# diferencial-733.net
KiCad netlist of a schematic drawn in EAGLE
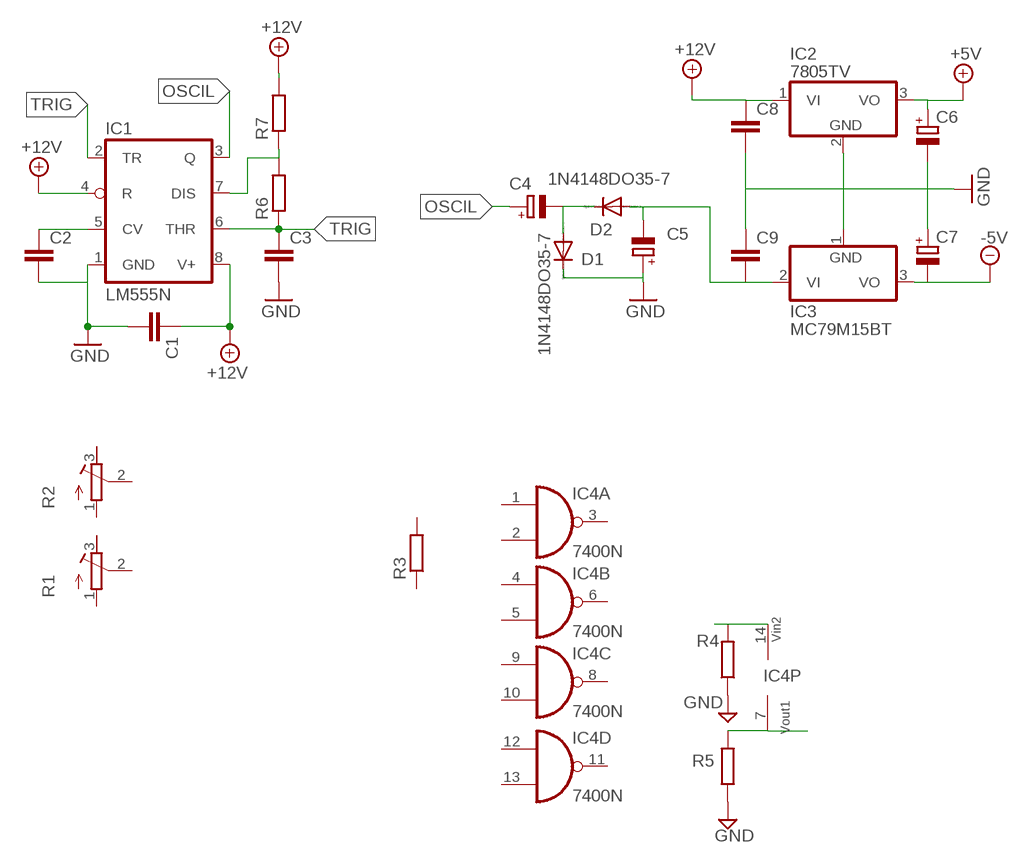
[diagram p0: schematic, sheet 1]

(export (version "E")
  (design (tool "Eeschema 10.0.6"))
  (components
    (comp (ref "C1")
      (value "C-EU050-025X075")
      (footprint "eagle-import:C050-025X075")
      (libsource (lib "eagle-import") (part "C-EU050-025X075"))
    )
    (comp (ref "C2")
      (value "C-EU050-025X075")
      (footprint "eagle-import:C050-025X075")
      (libsource (lib "eagle-import") (part "C-EU050-025X075"))
    )
    (comp (ref "C3")
      (value "C-EU025-025X050")
      (footprint "eagle-import:C025-025X050")
      (libsource (lib "eagle-import") (part "C-EU025-025X050"))
    )
    (comp (ref "C4")
      (value "CPOL-EUE2.5-6")
      (footprint "eagle-import:E2,5-6")
      (libsource (lib "eagle-import") (part "CPOL-EUE2.5-6"))
    )
    (comp (ref "C5")
      (value "CPOL-EUE2.5-7")
      (footprint "eagle-import:E2,5-7")
      (libsource (lib "eagle-import") (part "CPOL-EUE2.5-7"))
    )
    (comp (ref "C6")
      (value "CPOL-EUE2.5-5")
      (footprint "eagle-import:E2,5-5")
      (libsource (lib "eagle-import") (part "CPOL-EUE2.5-5"))
    )
    (comp (ref "C7")
      (value "CPOL-EUE2.5-5")
      (footprint "eagle-import:E2,5-5")
      (libsource (lib "eagle-import") (part "CPOL-EUE2.5-5"))
    )
    (comp (ref "C8")
      (value "C-EU025-025X050")
      (footprint "eagle-import:C025-025X050")
      (libsource (lib "eagle-import") (part "C-EU025-025X050"))
    )
    (comp (ref "C9")
      (value "C-EU025-025X050")
      (footprint "eagle-import:C025-025X050")
      (libsource (lib "eagle-import") (part "C-EU025-025X050"))
    )
    (comp (ref "D1")
      (value "1N4148DO35-7")
      (footprint "eagle-import:DO35-7")
      (libsource (lib "eagle-import") (part "1N4148DO35-7"))
    )
    (comp (ref "D2")
      (value "1N4148DO35-7")
      (footprint "eagle-import:DO35-7")
      (libsource (lib "eagle-import") (part "1N4148DO35-7"))
    )
    (comp (ref "IC1")
      (value "LM555N")
      (footprint "eagle-import:DIL08")
      (libsource (lib "eagle-import") (part "555NLM"))
    )
    (comp (ref "IC2")
      (value "7805TV")
      (footprint "eagle-import:TO220V")
      (libsource (lib "eagle-import") (part "78TV05"))
    )
    (comp (ref "IC3")
      (value "MC79M15BT")
      (footprint "eagle-import:TO220V")
      (libsource (lib "eagle-import") (part "MC79MT15B"))
    )
    (comp (ref "IC4")
      (value "7400N")
      (footprint "eagle-import:DIL14")
      (libsource (lib "eagle-import") (part "7400N"))
    )
    (comp (ref "R1")
      (value "R-TRIMM64W")
      (footprint "eagle-import:RTRIM64W")
      (libsource (lib "eagle-import") (part "R-TRIMM64W"))
    )
    (comp (ref "R2")
      (value "R-TRIMM64W")
      (footprint "eagle-import:RTRIM64W")
      (libsource (lib "eagle-import") (part "R-TRIMM64W"))
    )
    (comp (ref "R3")
      (value "R-EU_0207/7")
      (footprint "eagle-import:0207_7")
      (libsource (lib "eagle-import") (part "R-EU_0207/7"))
    )
    (comp (ref "R4")
      (value "R-EU_0207/7")
      (footprint "eagle-import:0207_7")
      (libsource (lib "eagle-import") (part "R-EU_0207/7"))
    )
    (comp (ref "R5")
      (value "R-EU_0207/7")
      (footprint "eagle-import:0207_7")
      (libsource (lib "eagle-import") (part "R-EU_0207/7"))
    )
    (comp (ref "R6")
      (value "R-EU_0207/7")
      (footprint "eagle-import:0207_7")
      (libsource (lib "eagle-import") (part "R-EU_0207/7"))
    )
    (comp (ref "R7")
      (value "R-EU_0207/7")
      (footprint "eagle-import:0207_7")
      (libsource (lib "eagle-import") (part "R-EU_0207/7"))
    )
  )
  (nets
    (net (code "1") (name "+5V") (class "Default")
      (node (ref "C6") (pin "+") (pinfunction "+_+") (pintype "passive"))
      (node (ref "IC2") (pin "3") (pinfunction "VO_3") (pintype "passive"))
    )
    (net (code "2") (name "+12V") (class "Default")
      (node (ref "C1") (pin "1") (pinfunction "1_1") (pintype "passive"))
      (node (ref "C8") (pin "1") (pinfunction "1_1") (pintype "passive"))
      (node (ref "IC1") (pin "4") (pinfunction "R_4") (pintype "input"))
      (node (ref "IC1") (pin "8") (pinfunction "V+_8") (pintype "power_in"))
      (node (ref "IC2") (pin "1") (pinfunction "VI_1") (pintype "input"))
      (node (ref "R7") (pin "2") (pinfunction "2_2") (pintype "passive"))
    )
    (net (code "3") (name "-5V") (class "Default")
      (node (ref "IC3") (pin "3") (pinfunction "VO_3") (pintype "passive"))
    )
    (net (code "4") (name "GND") (class "Default")
      (node (ref "C1") (pin "2") (pinfunction "2_2") (pintype "passive"))
      (node (ref "C2") (pin "2") (pinfunction "2_2") (pintype "passive"))
      (node (ref "C3") (pin "2") (pinfunction "2_2") (pintype "passive"))
      (node (ref "C5") (pin "+") (pinfunction "+_+") (pintype "passive"))
      (node (ref "C6") (pin "-") (pinfunction "-_-") (pintype "passive"))
      (node (ref "C7") (pin "+") (pinfunction "+_+") (pintype "passive"))
      (node (ref "C8") (pin "2") (pinfunction "2_2") (pintype "passive"))
      (node (ref "C9") (pin "1") (pinfunction "1_1") (pintype "passive"))
      (node (ref "D1") (pin "C") (pinfunction "C_C") (pintype "passive"))
      (node (ref "IC1") (pin "1") (pinfunction "GND_1") (pintype "power_in"))
      (node (ref "IC2") (pin "2") (pinfunction "GND_2") (pintype "passive"))
      (node (ref "IC3") (pin "1") (pinfunction "GND_1") (pintype "passive"))
      (node (ref "R4") (pin "1") (pinfunction "1_1") (pintype "passive"))
      (node (ref "R5") (pin "1") (pinfunction "1_1") (pintype "passive"))
    )
    (net (code "5") (name "Net-(C4-Pad-)") (class "Default")
      (node (ref "C4") (pin "-") (pinfunction "-_-") (pintype "passive"))
      (node (ref "D1") (pin "A") (pinfunction "A_A") (pintype "passive"))
      (node (ref "D2") (pin "C") (pinfunction "C_C") (pintype "passive"))
    )
    (net (code "6") (name "Net-(IC1-CV)") (class "Default")
      (node (ref "C2") (pin "1") (pinfunction "1_1") (pintype "passive"))
      (node (ref "IC1") (pin "5") (pinfunction "CV_5") (pintype "input"))
    )
    (net (code "7") (name "Net-(IC1-DIS)") (class "Default")
      (node (ref "IC1") (pin "7") (pinfunction "DIS_7") (pintype "input"))
      (node (ref "R6") (pin "2") (pinfunction "2_2") (pintype "passive"))
      (node (ref "R7") (pin "1") (pinfunction "1_1") (pintype "passive"))
    )
    (net (code "8") (name "Net-(IC3-VI)") (class "Default")
      (node (ref "C5") (pin "-") (pinfunction "-_-") (pintype "passive"))
      (node (ref "C9") (pin "2") (pinfunction "2_2") (pintype "passive"))
      (node (ref "D2") (pin "A") (pinfunction "A_A") (pintype "passive"))
      (node (ref "IC3") (pin "2") (pinfunction "VI_2") (pintype "input"))
    )
    (net (code "9") (name "Net-(IC4E-VCC)") (class "Default")
      (node (ref "IC4") (pin "14") (pinfunction "VCC_14") (pintype "power_in"))
      (node (ref "R4") (pin "2") (pinfunction "2_2") (pintype "passive"))
    )
    (net (code "10") (name "Net-(IC4E-VOUT2)") (class "Default")
      (node (ref "IC4") (pin "7") (pinfunction "VOUT2_7") (pintype "power_in"))
      (node (ref "R5") (pin "2") (pinfunction "2_2") (pintype "passive"))
    )
    (net (code "11") (name "OSCIL") (class "Default")
      (node (ref "C4") (pin "+") (pinfunction "+_+") (pintype "passive"))
      (node (ref "IC1") (pin "3") (pinfunction "Q_3") (pintype "output"))
    )
    (net (code "12") (name "TRIG") (class "Default")
      (node (ref "C3") (pin "1") (pinfunction "1_1") (pintype "passive"))
      (node (ref "IC1") (pin "2") (pinfunction "TR_2") (pintype "input"))
      (node (ref "IC1") (pin "6") (pinfunction "THR_6") (pintype "input"))
      (node (ref "R6") (pin "1") (pinfunction "1_1") (pintype "passive"))
    )
    (net (code "13") (name "unconnected-(C7-Pad-)") (class "Default")
      (node (ref "C7") (pin "-") (pinfunction "-_-") (pintype "passive"))
    )
    (net (code "14") (name "unconnected-(IC4A-I0-Pad1)") (class "Default")
      (node (ref "IC4") (pin "1") (pinfunction "I0_1") (pintype "input"))
    )
    (net (code "15") (name "unconnected-(IC4A-I1-Pad2)") (class "Default")
      (node (ref "IC4") (pin "2") (pinfunction "I1_2") (pintype "input"))
    )
    (net (code "16") (name "unconnected-(IC4A-O-Pad3)") (class "Default")
      (node (ref "IC4") (pin "3") (pinfunction "O_3") (pintype "output"))
    )
    (net (code "17") (name "unconnected-(IC4B-I0-Pad4)") (class "Default")
      (node (ref "IC4") (pin "4") (pinfunction "I0_4") (pintype "input"))
    )
    (net (code "18") (name "unconnected-(IC4B-I1-Pad5)") (class "Default")
      (node (ref "IC4") (pin "5") (pinfunction "I1_5") (pintype "input"))
    )
    (net (code "19") (name "unconnected-(IC4B-O-Pad6)") (class "Default")
      (node (ref "IC4") (pin "6") (pinfunction "O_6") (pintype "output"))
    )
    (net (code "20") (name "unconnected-(IC4C-I0-Pad9)") (class "Default")
      (node (ref "IC4") (pin "9") (pinfunction "I0_9") (pintype "input"))
    )
    (net (code "21") (name "unconnected-(IC4C-I1-Pad10)") (class "Default")
      (node (ref "IC4") (pin "10") (pinfunction "I1_10") (pintype "input"))
    )
    (net (code "22") (name "unconnected-(IC4C-O-Pad8)") (class "Default")
      (node (ref "IC4") (pin "8") (pinfunction "O_8") (pintype "output"))
    )
    (net (code "23") (name "unconnected-(IC4D-I0-Pad12)") (class "Default")
      (node (ref "IC4") (pin "12") (pinfunction "I0_12") (pintype "input"))
    )
    (net (code "24") (name "unconnected-(IC4D-I1-Pad13)") (class "Default")
      (node (ref "IC4") (pin "13") (pinfunction "I1_13") (pintype "input"))
    )
    (net (code "25") (name "unconnected-(IC4D-O-Pad11)") (class "Default")
      (node (ref "IC4") (pin "11") (pinfunction "O_11") (pintype "output"))
    )
    (net (code "26") (name "unconnected-(R1-A-Pad1)") (class "Default")
      (node (ref "R1") (pin "1") (pinfunction "A_1") (pintype "passive"))
    )
    (net (code "27") (name "unconnected-(R1-E-Pad3)") (class "Default")
      (node (ref "R1") (pin "3") (pinfunction "E_3") (pintype "passive"))
    )
    (net (code "28") (name "unconnected-(R1-S-Pad2)") (class "Default")
      (node (ref "R1") (pin "2") (pinfunction "S_2") (pintype "passive"))
    )
    (net (code "29") (name "unconnected-(R2-A-Pad1)") (class "Default")
      (node (ref "R2") (pin "1") (pinfunction "A_1") (pintype "passive"))
    )
    (net (code "30") (name "unconnected-(R2-E-Pad3)") (class "Default")
      (node (ref "R2") (pin "3") (pinfunction "E_3") (pintype "passive"))
    )
    (net (code "31") (name "unconnected-(R2-S-Pad2)") (class "Default")
      (node (ref "R2") (pin "2") (pinfunction "S_2") (pintype "passive"))
    )
    (net (code "32") (name "unconnected-(R3-Pad1)") (class "Default")
      (node (ref "R3") (pin "1") (pinfunction "1_1") (pintype "passive"))
    )
    (net (code "33") (name "unconnected-(R3-Pad2)") (class "Default")
      (node (ref "R3") (pin "2") (pinfunction "2_2") (pintype "passive"))
    )
  )
)
